# OnePinKeypadv1_1_0.net
KiCad netlist of a schematic drawn in EAGLE
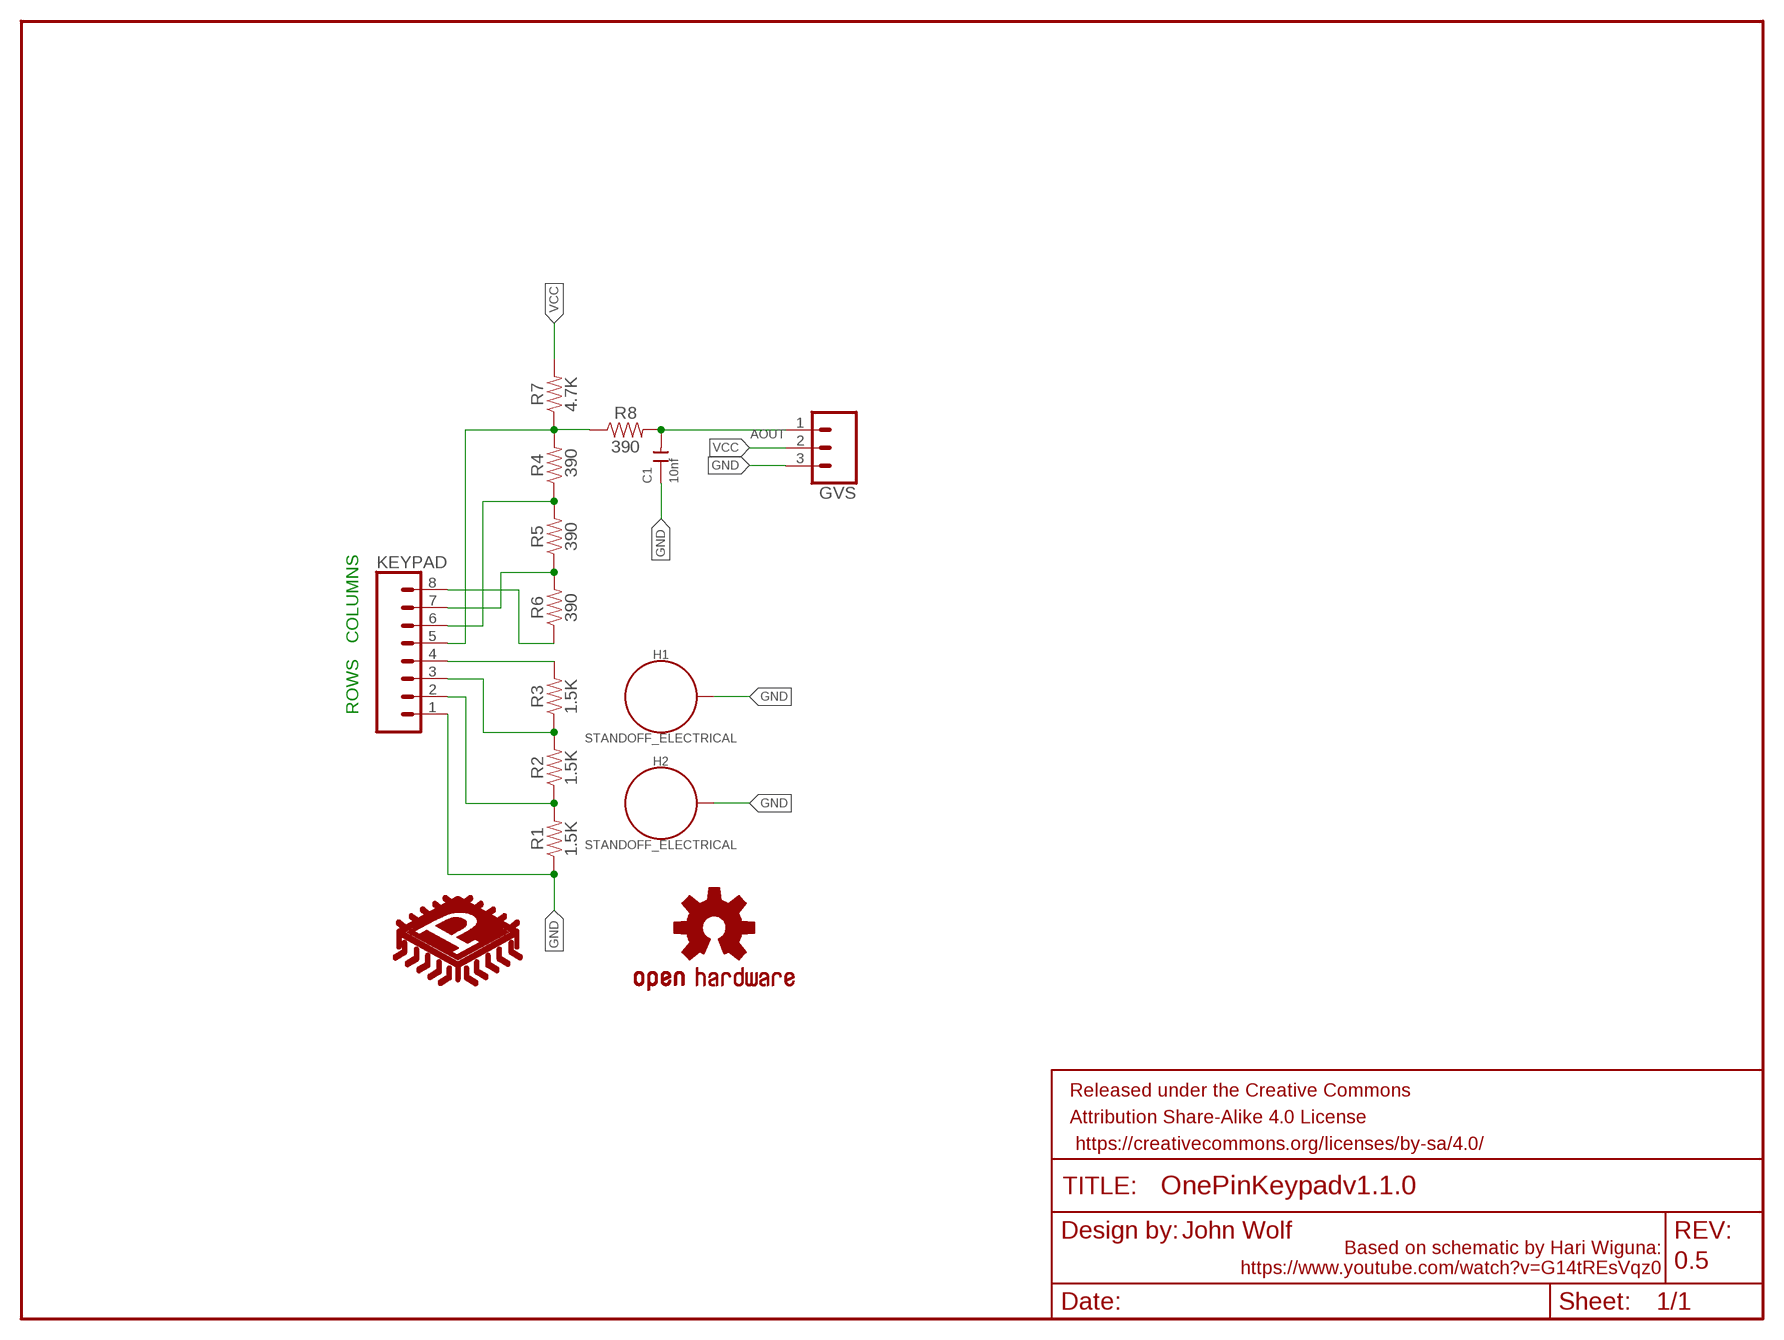
[diagram p0: schematic, sheet 1]

(export (version "E")
  (design (tool "Eeschema 10.0.6"))
  (components
    (comp (ref "C1")
      (value "10nf")
      (footprint "eagle-import:C0805")
      (fields (field (name "MPN") "CC0805KRX7R9BB104"))
      (libsource (lib "eagle-import") (part "CERAMIC-100NF-50V-10%-X7R(0805)"))
    )
    (comp (ref "FRAME1")
      (value "FRAME-LETTER")
      (footprint "eagle-import:CREATIVE_COMMONS")
      (libsource (lib "eagle-import") (part "FRAME-LETTER"))
    )
    (comp (ref "GVS")
      (value "CONN_03")
      (footprint "eagle-import:1X03")
      (libsource (lib "eagle-import") (part "CONN_03"))
    )
    (comp (ref "H1")
      (value "STANDOFF_ELECTRICAL")
      (footprint "eagle-import:STANDOFF-ELECTRICAL")
      (libsource (lib "eagle-import") (part "STANDOFF_ELECTRICAL"))
    )
    (comp (ref "H2")
      (value "STANDOFF_ELECTRICAL")
      (footprint "eagle-import:STANDOFF-ELECTRICAL")
      (libsource (lib "eagle-import") (part "STANDOFF_ELECTRICAL"))
    )
    (comp (ref "KEYPAD")
      (value "CONN_08\"")
      (footprint "eagle-import:1X08")
      (libsource (lib "eagle-import") (part "CONN_08{dblquote}"))
    )
    (comp (ref "LOGO1")
      (value "OSHW-LOGOS")
      (footprint "eagle-import:OSHW-LOGO-S")
      (libsource (lib "eagle-import") (part "OSHW-LOGOS"))
    )
    (comp (ref "R1")
      (value "1.5K")
      (footprint "eagle-import:0805")
      (libsource (lib "eagle-import") (part "RESISTOR0805"))
    )
    (comp (ref "R2")
      (value "1.5K")
      (footprint "eagle-import:0805")
      (libsource (lib "eagle-import") (part "RESISTOR0805"))
    )
    (comp (ref "R3")
      (value "1.5K")
      (footprint "eagle-import:0805")
      (libsource (lib "eagle-import") (part "RESISTOR0805"))
    )
    (comp (ref "R4")
      (value "390")
      (footprint "eagle-import:0805")
      (libsource (lib "eagle-import") (part "RESISTOR0805"))
    )
    (comp (ref "R5")
      (value "390")
      (footprint "eagle-import:0805")
      (libsource (lib "eagle-import") (part "RESISTOR0805"))
    )
    (comp (ref "R6")
      (value "390")
      (footprint "eagle-import:0805")
      (libsource (lib "eagle-import") (part "RESISTOR0805"))
    )
    (comp (ref "R7")
      (value "4.7K")
      (footprint "eagle-import:0805")
      (libsource (lib "eagle-import") (part "RESISTOR0805"))
    )
    (comp (ref "R8")
      (value "390")
      (footprint "eagle-import:0805")
      (libsource (lib "eagle-import") (part "RESISTOR0805"))
    )
    (comp (ref "U$2")
      (value "LOGO_V1")
      (footprint "eagle-import:LOGO_V1")
      (libsource (lib "eagle-import") (part "LOGO_V1"))
    )
  )
  (nets
    (net (code "1") (name "/AOUT") (class "Default")
      (node (ref "C1") (pin "2") (pinfunction "2_2") (pintype "passive"))
      (node (ref "GVS") (pin "1") (pinfunction "1_1") (pintype "passive"))
      (node (ref "R8") (pin "2") (pinfunction "2_2") (pintype "passive"))
    )
    (net (code "2") (name "GND") (class "Default")
      (node (ref "C1") (pin "1") (pinfunction "1_1") (pintype "passive"))
      (node (ref "GVS") (pin "3") (pinfunction "3_3") (pintype "passive"))
      (node (ref "H1") (pin "P1") (pinfunction "P$1_P1") (pintype "bidirectional"))
      (node (ref "H2") (pin "P1") (pinfunction "P$1_P1") (pintype "bidirectional"))
      (node (ref "KEYPAD") (pin "1") (pinfunction "1_1") (pintype "passive"))
      (node (ref "R1") (pin "1") (pinfunction "1_1") (pintype "passive"))
    )
    (net (code "3") (name "Net-(KEYPAD-Pad2)") (class "Default")
      (node (ref "KEYPAD") (pin "2") (pinfunction "2_2") (pintype "passive"))
      (node (ref "R1") (pin "2") (pinfunction "2_2") (pintype "passive"))
      (node (ref "R2") (pin "1") (pinfunction "1_1") (pintype "passive"))
    )
    (net (code "4") (name "Net-(KEYPAD-Pad3)") (class "Default")
      (node (ref "KEYPAD") (pin "3") (pinfunction "3_3") (pintype "passive"))
      (node (ref "R2") (pin "2") (pinfunction "2_2") (pintype "passive"))
      (node (ref "R3") (pin "1") (pinfunction "1_1") (pintype "passive"))
    )
    (net (code "5") (name "Net-(KEYPAD-Pad4)") (class "Default")
      (node (ref "KEYPAD") (pin "4") (pinfunction "4_4") (pintype "passive"))
      (node (ref "R3") (pin "2") (pinfunction "2_2") (pintype "passive"))
    )
    (net (code "6") (name "Net-(KEYPAD-Pad5)") (class "Default")
      (node (ref "KEYPAD") (pin "5") (pinfunction "5_5") (pintype "passive"))
      (node (ref "R4") (pin "2") (pinfunction "2_2") (pintype "passive"))
      (node (ref "R7") (pin "1") (pinfunction "1_1") (pintype "passive"))
      (node (ref "R8") (pin "1") (pinfunction "1_1") (pintype "passive"))
    )
    (net (code "7") (name "Net-(KEYPAD-Pad6)") (class "Default")
      (node (ref "KEYPAD") (pin "6") (pinfunction "6_6") (pintype "passive"))
      (node (ref "R4") (pin "1") (pinfunction "1_1") (pintype "passive"))
      (node (ref "R5") (pin "2") (pinfunction "2_2") (pintype "passive"))
    )
    (net (code "8") (name "Net-(KEYPAD-Pad7)") (class "Default")
      (node (ref "KEYPAD") (pin "7") (pinfunction "7_7") (pintype "passive"))
      (node (ref "R5") (pin "1") (pinfunction "1_1") (pintype "passive"))
      (node (ref "R6") (pin "2") (pinfunction "2_2") (pintype "passive"))
    )
    (net (code "9") (name "Net-(KEYPAD-Pad8)") (class "Default")
      (node (ref "KEYPAD") (pin "8") (pinfunction "8_8") (pintype "passive"))
      (node (ref "R6") (pin "1") (pinfunction "1_1") (pintype "passive"))
    )
    (net (code "10") (name "VCC") (class "Default")
      (node (ref "GVS") (pin "2") (pinfunction "2_2") (pintype "passive"))
      (node (ref "R7") (pin "2") (pinfunction "2_2") (pintype "passive"))
    )
  )
)
